# LNA_RF_Sch.net
KiCad netlist of a schematic drawn in Altium Designer
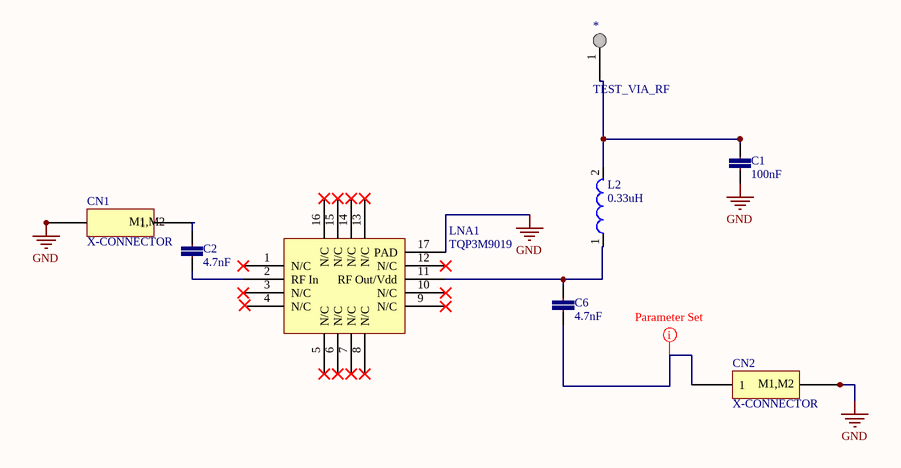
[diagram p0: LNA_RF_Sch.SchDoc]

(export (version "E")
  (design (tool "Eeschema 10.0.6"))
  (components
    (comp (ref "*")
      (value "TEST_VIA_RF")
      (footprint "New footprint 1")
      (description "Test VIA for RF circuits")
      (libsource (lib "IMBEL") (part "TEST_VIA"))
    )
    (comp (ref "C1")
      (value "100nF")
      (footprint "CAPC0603(1608)55_L")
      (description "CAP CER 0.1UF 50V X7R 0603")
      (fields (field (name "PART NO") "GRM188R71H104KA93D"))
      (libsource (lib "IMBEL") (part "CAPACITOR"))
    )
    (comp (ref "C2")
      (value "4.7nF")
      (footprint "CAPC0603(1608)55_L")
      (description "CAP CER 4700PF 50V 20% X7R 0603")
      (fields (field (name "PART NO") "GRM188R71H472MA01D"))
      (libsource (lib "IMBEL") (part "CAPACITOR"))
    )
    (comp (ref "C6")
      (value "4.7nF")
      (footprint "CAPC0603(1608)55_L")
      (description "CAP CER 4700PF 50V 20% X7R 0603")
      (fields (field (name "PART NO") "GRM188R71H472MA01D"))
      (libsource (lib "IMBEL") (part "CAPACITOR"))
    )
    (comp (ref "CN1")
      (value "X-CONNECTOR")
      (footprint "X-CONNECTOR-PCB")
      (description "CONECTOR PARA MÓDULOS X MICROWAVE")
      (libsource (lib "(LR)²") (part "X-CONNECTOR"))
    )
    (comp (ref "CN2")
      (value "X-CONNECTOR")
      (footprint "X-CONNECTOR-PCB")
      (description "CONECTOR PARA MÓDULOS X MICROWAVE")
      (libsource (lib "") (part "X-CONNECTOR_1"))
    )
    (comp (ref "L2")
      (value "0.33uH")
      (footprint "0603-IND")
      (description "Fixed Inductors RF Chip Inductor 0.33 uH 5 % 0.56 A")
      (fields (field (name "PART NO") "0603LS-331XJLB"))
      (libsource (lib "IMBEL") (part "INDUTOR"))
    )
    (comp (ref "LNA1")
      (value "TQP3M9019")
      (footprint "QFN50P300X300X90_HS-17N")
      (description "RF Amplifier .05-4GHz P1dB= 22dB Gain 26.4dB 5Volts")
      (libsource (lib "IMBEL") (part "TQP3M9019"))
    )
  )
  (nets
    (net (code "1") (name "GND") (class "Default")
      (node (ref "C1") (pin "2") (pinfunction "2_2") (pintype "passive"))
      (node (ref "CN1") (pin "M1") (pinfunction "M1_M1") (pintype "passive"))
      (node (ref "CN1") (pin "M2") (pinfunction "M2_M2") (pintype "passive"))
      (node (ref "CN2") (pin "M1") (pinfunction "M1_M1") (pintype "passive"))
      (node (ref "CN2") (pin "M2") (pinfunction "M2_M2") (pintype "passive"))
      (node (ref "LNA1") (pin "17") (pinfunction "PAD_17") (pintype "passive"))
    )
    (net (code "2") (name "Net-(*-Pad1)") (class "Default")
      (node (ref "*") (pin "1") (pinfunction "1_1") (pintype "passive"))
      (node (ref "C1") (pin "1") (pinfunction "1_1") (pintype "passive"))
      (node (ref "L2") (pin "2") (pinfunction "2_2") (pintype "passive"))
    )
    (net (code "3") (name "Net-(C2-Pad1)") (class "Default")
      (node (ref "C2") (pin "1") (pinfunction "1_1") (pintype "passive"))
      (node (ref "CN1") (pin "1") (pinfunction "1_1") (pintype "passive"))
    )
    (net (code "4") (name "Net-(C6-Pad2)") (class "Default")
      (node (ref "C6") (pin "2") (pinfunction "2_2") (pintype "passive"))
      (node (ref "CN2") (pin "1") (pinfunction "1_1") (pintype "passive"))
    )
    (net (code "5") (name "Net-(LNA1-RF_In)") (class "Default")
      (node (ref "C2") (pin "2") (pinfunction "2_2") (pintype "passive"))
      (node (ref "LNA1") (pin "2") (pinfunction "RF_In_2") (pintype "passive"))
    )
    (net (code "6") (name "Net-(LNA1-RF_Out{slash}Vdd)") (class "Default")
      (node (ref "C6") (pin "1") (pinfunction "1_1") (pintype "passive"))
      (node (ref "L2") (pin "1") (pinfunction "1_1") (pintype "passive"))
      (node (ref "LNA1") (pin "11") (pinfunction "RF_Out/Vdd_11") (pintype "passive"))
    )
    (net (code "7") (name "unconnected-(LNA1-N{slash}C-Pad1)") (class "Default")
      (node (ref "LNA1") (pin "1") (pinfunction "N/C_1") (pintype "passive+no_connect"))
    )
    (net (code "8") (name "unconnected-(LNA1-N{slash}C-Pad3)") (class "Default")
      (node (ref "LNA1") (pin "3") (pinfunction "N/C_3") (pintype "passive+no_connect"))
    )
    (net (code "9") (name "unconnected-(LNA1-N{slash}C-Pad4)") (class "Default")
      (node (ref "LNA1") (pin "4") (pinfunction "N/C_4") (pintype "passive"))
    )
    (net (code "10") (name "unconnected-(LNA1-N{slash}C-Pad5)") (class "Default")
      (node (ref "LNA1") (pin "5") (pinfunction "N/C_5") (pintype "passive+no_connect"))
    )
    (net (code "11") (name "unconnected-(LNA1-N{slash}C-Pad6)") (class "Default")
      (node (ref "LNA1") (pin "6") (pinfunction "N/C_6") (pintype "passive+no_connect"))
    )
    (net (code "12") (name "unconnected-(LNA1-N{slash}C-Pad7)") (class "Default")
      (node (ref "LNA1") (pin "7") (pinfunction "N/C_7") (pintype "passive+no_connect"))
    )
    (net (code "13") (name "unconnected-(LNA1-N{slash}C-Pad8)") (class "Default")
      (node (ref "LNA1") (pin "8") (pinfunction "N/C_8") (pintype "passive+no_connect"))
    )
    (net (code "14") (name "unconnected-(LNA1-N{slash}C-Pad9)") (class "Default")
      (node (ref "LNA1") (pin "9") (pinfunction "N/C_9") (pintype "passive+no_connect"))
    )
    (net (code "15") (name "unconnected-(LNA1-N{slash}C-Pad10)") (class "Default")
      (node (ref "LNA1") (pin "10") (pinfunction "N/C_10") (pintype "passive+no_connect"))
    )
    (net (code "16") (name "unconnected-(LNA1-N{slash}C-Pad12)") (class "Default")
      (node (ref "LNA1") (pin "12") (pinfunction "N/C_12") (pintype "passive+no_connect"))
    )
    (net (code "17") (name "unconnected-(LNA1-N{slash}C-Pad13)") (class "Default")
      (node (ref "LNA1") (pin "13") (pinfunction "N/C_13") (pintype "passive+no_connect"))
    )
    (net (code "18") (name "unconnected-(LNA1-N{slash}C-Pad14)") (class "Default")
      (node (ref "LNA1") (pin "14") (pinfunction "N/C_14") (pintype "passive+no_connect"))
    )
    (net (code "19") (name "unconnected-(LNA1-N{slash}C-Pad15)") (class "Default")
      (node (ref "LNA1") (pin "15") (pinfunction "N/C_15") (pintype "passive+no_connect"))
    )
    (net (code "20") (name "unconnected-(LNA1-N{slash}C-Pad16)") (class "Default")
      (node (ref "LNA1") (pin "16") (pinfunction "N/C_16") (pintype "passive+no_connect"))
    )
  )
)
